# Sensing.net
KiCad netlist of a schematic drawn in Altium Designer
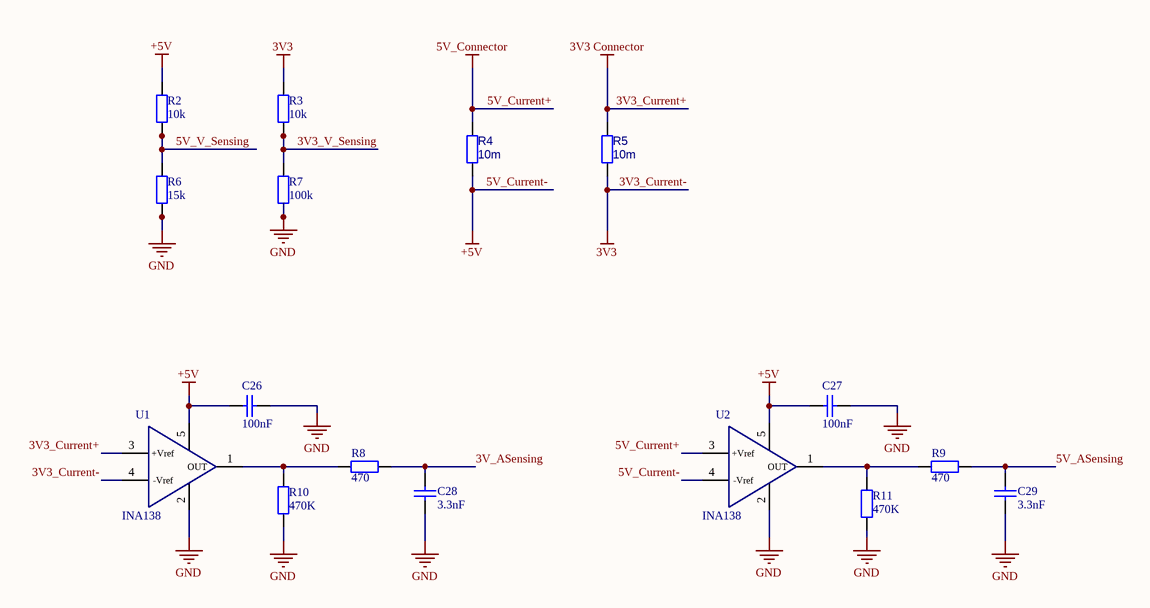
[diagram p0: Sensing.SchDoc]

(export (version "E")
  (design (tool "Eeschema 10.0.6"))
  (components
    (comp (ref "C26")
      (value "100nF")
      (footprint "WCAP-CSGP_0603_L1.6W0.8H0.8_Reflow")
      (description "WCAP-CSGP Multilayer Ceramic Chip Capacitor, General Purpose, size 0603, X7R, 100nF, 25VDC")
      (fields
        (field (name "MANUFACTURER") "Wurth Elektronik")
        (field (name "MANUFACTURER PART NUMBER") "885012206071")
      )
      (libsource (lib "LEEM UPM") (part "885012209047R"))
    )
    (comp (ref "C27")
      (value "100nF")
      (footprint "WCAP-CSGP_0603_L1.6W0.8H0.8_Reflow")
      (description "WCAP-CSGP Multilayer Ceramic Chip Capacitor, General Purpose, size 0603, X7R, 100nF, 25VDC")
      (fields
        (field (name "MANUFACTURER") "Wurth Elektronik")
        (field (name "MANUFACTURER PART NUMBER") "885012206071")
      )
      (libsource (lib "LEEM UPM") (part "885012209047R"))
    )
    (comp (ref "C28")
      (value "3.3nF")
      (footprint "WCAP-CSGP_0603_L1.6W0.8H0.8_Reflow")
      (description "WCAP-CSGP Multilayer Ceramic Chip Capacitor, General Purpose, size 0603, X7R, 3.3nF, 25VDC")
      (fields
        (field (name "MANUFACTURER") "Wurth Elektronik")
        (field (name "MANUFACTURER PART NUMBER") "885012206062")
      )
      (libsource (lib "LEEM UPM") (part "885012209047R"))
    )
    (comp (ref "C29")
      (value "3.3nF")
      (footprint "WCAP-CSGP_0603_L1.6W0.8H0.8_Reflow")
      (description "WCAP-CSGP Multilayer Ceramic Chip Capacitor, General Purpose, size 0603, X7R, 3.3nF, 25VDC")
      (fields
        (field (name "MANUFACTURER") "Wurth Elektronik")
        (field (name "MANUFACTURER PART NUMBER") "885012206062")
      )
      (libsource (lib "LEEM UPM") (part "885012209047R"))
    )
    (comp (ref "R2")
      (value "10k")
      (footprint "WRIS-RSKS_0603_Reflow")
      (description "WRIS-RSKS Thick Film Resistor, size 0603, 10000Ohm, 100mW")
      (fields
        (field (name "MANUFACTURER") "Wurth Elektronik")
        (field (name "MANUFACTURER PART NUMBER") "560112116005")
      )
      (libsource (lib "LEEM UPM") (part "560112140010"))
    )
    (comp (ref "R3")
      (value "10k")
      (footprint "WRIS-RSKS_0603_Reflow")
      (description "WRIS-RSKS Thick Film Resistor, size 0603, 10000Ohm, 100mW")
      (fields
        (field (name "MANUFACTURER") "Wurth Elektronik")
        (field (name "MANUFACTURER PART NUMBER") "560112116005")
      )
      (libsource (lib "LEEM UPM") (part "560112140010"))
    )
    (comp (ref "R4")
      (value "10m")
      (footprint "580070763010-Footprint-1")
      (description "Res, 0R01, 1%, 2W, Metal Foil, 0612 Rohs Compliant: Yes")
      (libsource (lib "LEEM UPM") (part "RES-2"))
    )
    (comp (ref "R5")
      (value "10m")
      (footprint "580070763010-Footprint-1")
      (description "Res, 0R01, 1%, 2W, Metal Foil, 0612 Rohs Compliant: Yes")
      (libsource (lib "LEEM UPM") (part "RES-2"))
    )
    (comp (ref "R6")
      (value "15k")
      (footprint "WRIS-RSKS_0603_Reflow")
      (description "WRIS-RSKS Thick Film Resistor, size 0603, 15000Ohm, 100mW")
      (fields
        (field (name "MANUFACTURER") "Wurth Elektronik")
        (field (name "MANUFACTURER PART NUMBER") "560112116035")
      )
      (libsource (lib "LEEM UPM") (part "560112140010"))
    )
    (comp (ref "R7")
      (value "100k")
      (footprint "WRIS-RSKS_0603_Reflow")
      (description "WRIS-RSKS Thick Film Resistor, size 0603, 100000Ohm, 100mW")
      (fields
        (field (name "MANUFACTURER PART NUMBER") "560112116004")
        (field (name "MANUFACTURER") "Wurth Elektronik")
      )
      (libsource (lib "LEEM UPM") (part "560112140010"))
    )
    (comp (ref "R8")
      (value "470")
      (footprint "WRIS-RSKS_0603_Reflow")
      (description "WRIS-RSKS Thick Film Resistor, size 0603, 470Ohm, 100mW")
      (fields
        (field (name "MANUFACTURER") "Wurth Elektronik")
        (field (name "MANUFACTURER PART NUMBER") "560112116067")
      )
      (libsource (lib "") (part "560112140010_1"))
    )
    (comp (ref "R9")
      (value "470")
      (footprint "WRIS-RSKS_0603_Reflow")
      (description "WRIS-RSKS Thick Film Resistor, size 0603, 470Ohm, 100mW")
      (fields
        (field (name "MANUFACTURER") "Wurth Elektronik")
        (field (name "MANUFACTURER PART NUMBER") "560112116067")
      )
      (libsource (lib "") (part "560112140010_1"))
    )
    (comp (ref "R10")
      (value "470K")
      (footprint "WRIS-RSKS_0603_Reflow")
      (description "WRIS-RSKS Thick Film Resistor, size 0603, 470000Ohm, 100mW")
      (fields
        (field (name "MANUFACTURER") "Wurth Elektronik")
        (field (name "MANUFACTURER PART NUMBER") "560112116019")
      )
      (libsource (lib "LEEM UPM") (part "560112140010"))
    )
    (comp (ref "R11")
      (value "470K")
      (footprint "WRIS-RSKS_0603_Reflow")
      (description "WRIS-RSKS Thick Film Resistor, size 0603, 470000Ohm, 100mW")
      (fields
        (field (name "MANUFACTURER") "Wurth Elektronik")
        (field (name "MANUFACTURER PART NUMBER") "560112116019")
      )
      (libsource (lib "LEEM UPM") (part "560112140010"))
    )
    (comp (ref "U1")
      (value "INA138")
      (footprint "INA138-Footprint-1")
      (description "Shunt Current Measure Amplifier")
      (fields
        (field (name "MANUFACTURER") "Texas Instruments")
        (field (name "MANUFACTURER PART NUMBER") "INA138NA/3K")
      )
      (libsource (lib "LEEM UPM") (part "INA138-Symbol-1"))
    )
    (comp (ref "U2")
      (value "INA138")
      (footprint "INA138-Footprint-1")
      (description "Shunt Current Measure Amplifier")
      (fields
        (field (name "MANUFACTURER") "Texas Instruments")
        (field (name "MANUFACTURER PART NUMBER") "INA138NA/3K")
      )
      (libsource (lib "LEEM UPM") (part "INA138-Symbol-1"))
    )
  )
  (nets
    (net (code "1") (name "+5V") (class "Default")
      (node (ref "C26") (pin "2") (pinfunction "2_2") (pintype "passive"))
      (node (ref "C27") (pin "2") (pinfunction "2_2") (pintype "passive"))
      (node (ref "R2") (pin "2") (pinfunction "2_2") (pintype "passive"))
      (node (ref "R4") (pin "1") (pinfunction "1_1") (pintype "passive"))
      (node (ref "U1") (pin "5") (pinfunction "V+_5") (pintype "passive"))
      (node (ref "U2") (pin "4") (pinfunction "-Vref_4") (pintype "passive"))
      (node (ref "U2") (pin "5") (pinfunction "V+_5") (pintype "passive"))
    )
    (net (code "2") (name "/3V3_V_Sensing") (class "Default")
      (node (ref "R3") (pin "1") (pinfunction "1_1") (pintype "passive"))
      (node (ref "R7") (pin "2") (pinfunction "2_2") (pintype "passive"))
    )
    (net (code "3") (name "/3V_ASensing") (class "Default")
      (node (ref "C28") (pin "2") (pinfunction "2_2") (pintype "passive"))
      (node (ref "R8") (pin "2") (pinfunction "2_2") (pintype "passive"))
    )
    (net (code "4") (name "/5V_ASensing") (class "Default")
      (node (ref "C29") (pin "2") (pinfunction "2_2") (pintype "passive"))
      (node (ref "R9") (pin "2") (pinfunction "2_2") (pintype "passive"))
    )
    (net (code "5") (name "/5V_V_Sensing") (class "Default")
      (node (ref "R2") (pin "1") (pinfunction "1_1") (pintype "passive"))
      (node (ref "R6") (pin "2") (pinfunction "2_2") (pintype "passive"))
    )
    (net (code "6") (name "3V3") (class "Default")
      (node (ref "R3") (pin "2") (pinfunction "2_2") (pintype "passive"))
      (node (ref "R5") (pin "1") (pinfunction "1_1") (pintype "passive"))
      (node (ref "U1") (pin "4") (pinfunction "-Vref_4") (pintype "passive"))
    )
    (net (code "7") (name "3V3 Connector") (class "Default")
      (node (ref "R5") (pin "2") (pinfunction "2_2") (pintype "passive"))
      (node (ref "U1") (pin "3") (pinfunction "+Vref_3") (pintype "passive"))
    )
    (net (code "8") (name "5V_Connector") (class "Default")
      (node (ref "R4") (pin "2") (pinfunction "2_2") (pintype "passive"))
      (node (ref "U2") (pin "3") (pinfunction "+Vref_3") (pintype "passive"))
    )
    (net (code "9") (name "GND") (class "Default")
      (node (ref "C26") (pin "1") (pinfunction "1_1") (pintype "passive"))
      (node (ref "C27") (pin "1") (pinfunction "1_1") (pintype "passive"))
      (node (ref "C28") (pin "1") (pinfunction "1_1") (pintype "passive"))
      (node (ref "C29") (pin "1") (pinfunction "1_1") (pintype "passive"))
      (node (ref "R10") (pin "1") (pinfunction "1_1") (pintype "passive"))
      (node (ref "R11") (pin "1") (pinfunction "1_1") (pintype "passive"))
      (node (ref "R6") (pin "1") (pinfunction "1_1") (pintype "passive"))
      (node (ref "R7") (pin "1") (pinfunction "1_1") (pintype "passive"))
      (node (ref "U1") (pin "2") (pinfunction "GND_2") (pintype "passive"))
      (node (ref "U2") (pin "2") (pinfunction "GND_2") (pintype "passive"))
    )
    (net (code "10") (name "Net-(U1-OUT)") (class "Default")
      (node (ref "R10") (pin "2") (pinfunction "2_2") (pintype "passive"))
      (node (ref "R8") (pin "1") (pinfunction "1_1") (pintype "passive"))
      (node (ref "U1") (pin "1") (pinfunction "OUT_1") (pintype "passive"))
    )
    (net (code "11") (name "Net-(U2-OUT)") (class "Default")
      (node (ref "R11") (pin "2") (pinfunction "2_2") (pintype "passive"))
      (node (ref "R9") (pin "1") (pinfunction "1_1") (pintype "passive"))
      (node (ref "U2") (pin "1") (pinfunction "OUT_1") (pintype "passive"))
    )
  )
)
